# TABBx_Lure_1_0.net
KiCad netlist of a schematic drawn in EAGLE
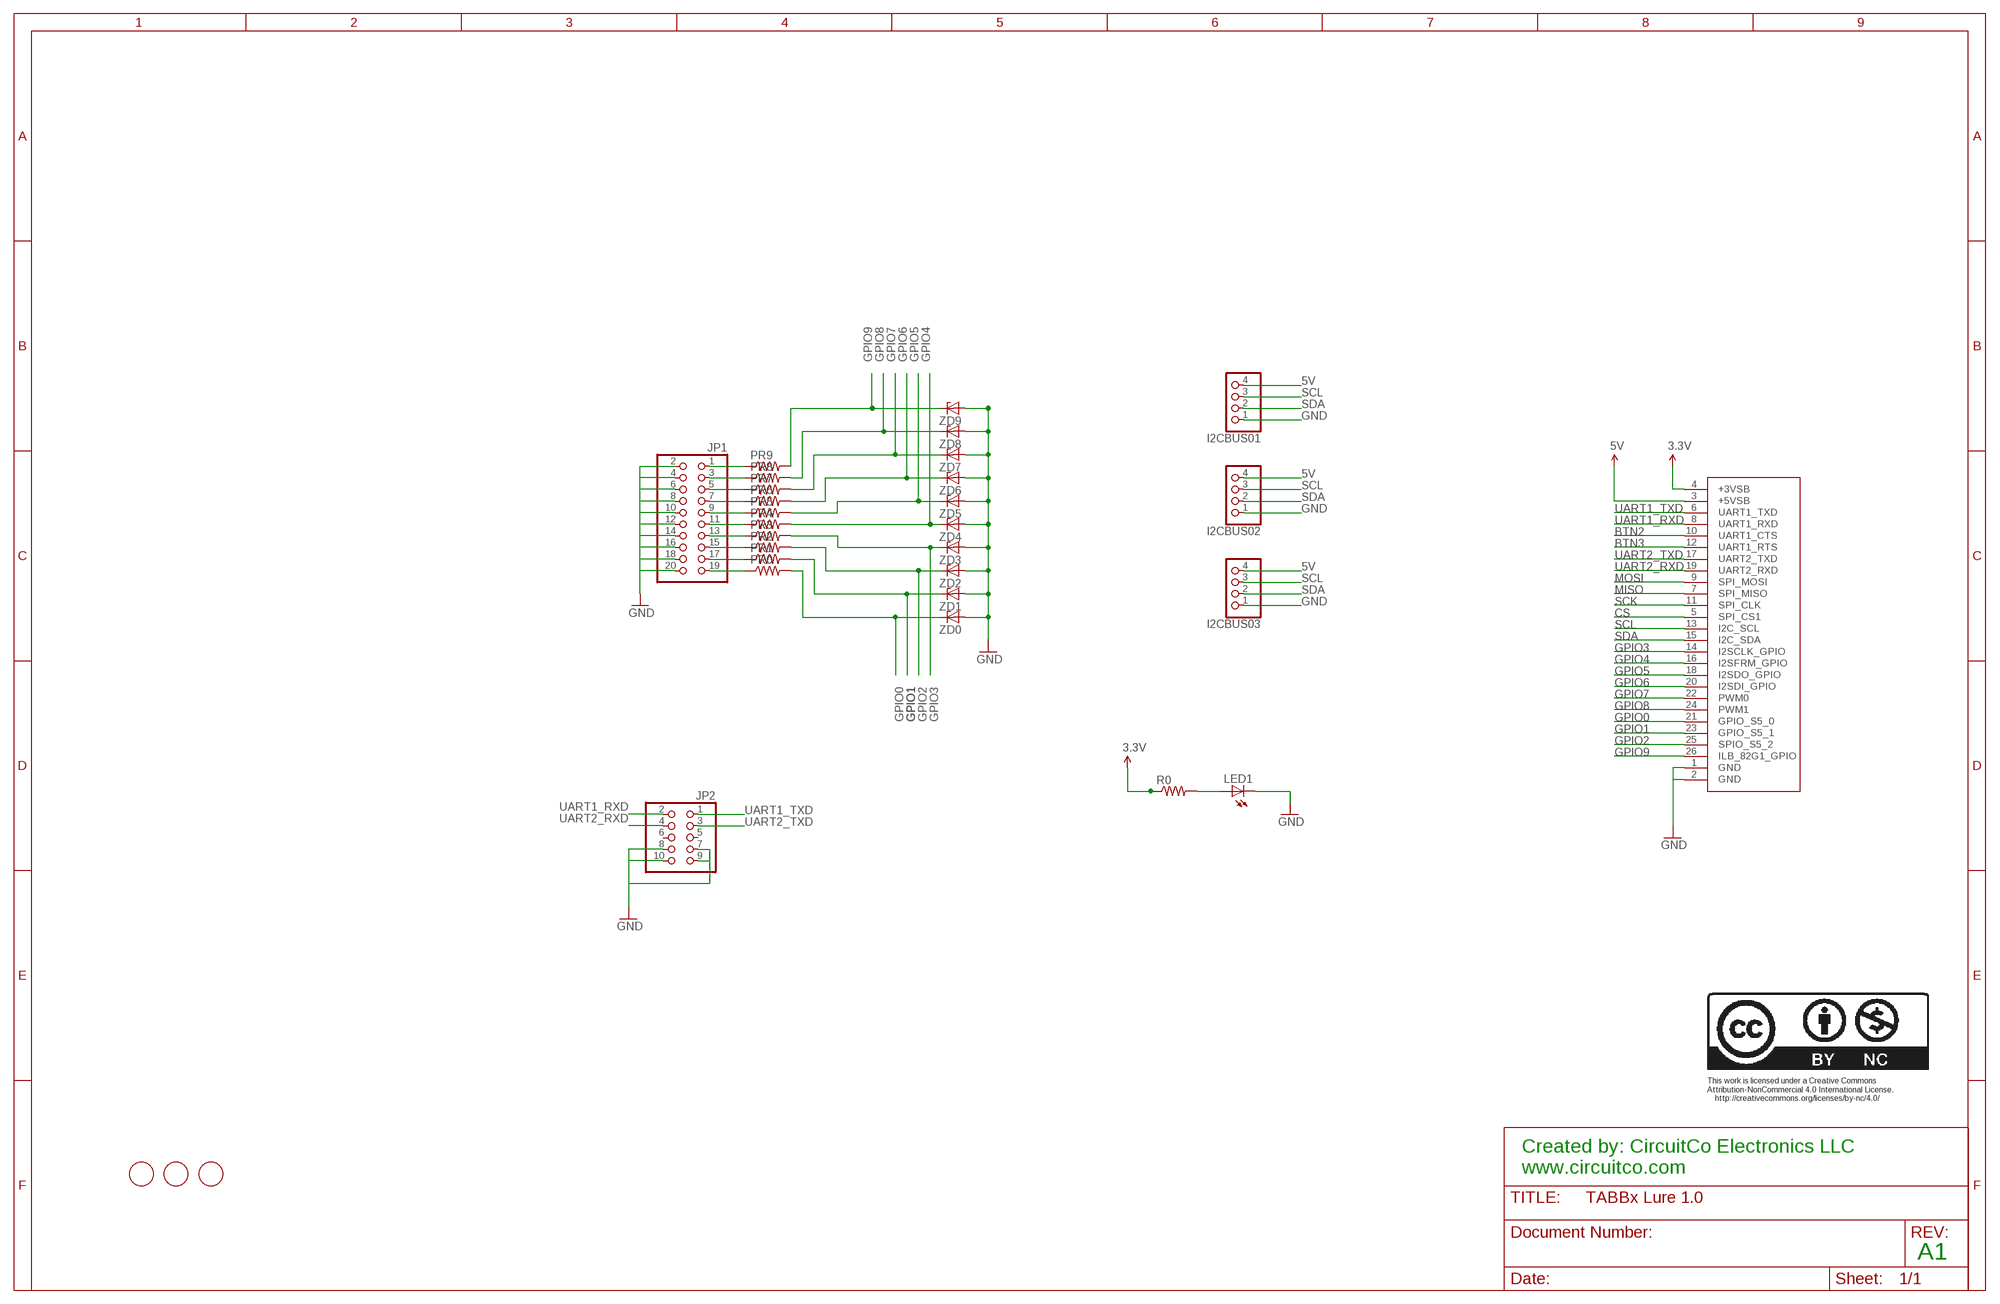
[diagram p0: schematic, sheet 1]

(export (version "E")
  (design (tool "Eeschema 10.0.6"))
  (components
    (comp (ref "I2CBUS01")
      (value "PINHD-1X4")
      (footprint "eagle-import:1X04")
      (libsource (lib "eagle-import") (part "PINHD-1X4"))
    )
    (comp (ref "I2CBUS02")
      (value "PINHD-1X4")
      (footprint "eagle-import:1X04")
      (libsource (lib "eagle-import") (part "PINHD-1X4"))
    )
    (comp (ref "I2CBUS03")
      (value "PINHD-1X4")
      (footprint "eagle-import:1X04")
      (libsource (lib "eagle-import") (part "PINHD-1X4"))
    )
    (comp (ref "JP1")
      (value "PINHD-2X10/90")
      (footprint "eagle-import:2X10_90")
      (libsource (lib "eagle-import") (part "PINHD-2X10/90"))
    )
    (comp (ref "JP2")
      (value "PINHD-2X5/90")
      (footprint "eagle-import:2X05_90")
      (libsource (lib "eagle-import") (part "PINHD-2X5/90"))
    )
    (comp (ref "JP4")
      (value "MINNOW2_LOW_SPEED")
      (footprint "eagle-import:MINNOWBOARD_2_LOW_SPEED")
      (libsource (lib "eagle-import") (part "MINNOW2_LOW_SPEED"))
    )
    (comp (ref "LED1")
      (value "LEDCHIPLED_1206")
      (footprint "eagle-import:CHIPLED_1206")
      (libsource (lib "eagle-import") (part "LEDCHIPLED_1206"))
    )
    (comp (ref "PR0")
      (value "R-US_M1206")
      (footprint "eagle-import:M1206")
      (libsource (lib "eagle-import") (part "R-US_M1206"))
    )
    (comp (ref "PR1")
      (value "R-US_M1206")
      (footprint "eagle-import:M1206")
      (libsource (lib "eagle-import") (part "R-US_M1206"))
    )
    (comp (ref "PR2")
      (value "R-US_M1206")
      (footprint "eagle-import:M1206")
      (libsource (lib "eagle-import") (part "R-US_M1206"))
    )
    (comp (ref "PR3")
      (value "R-US_M1206")
      (footprint "eagle-import:M1206")
      (libsource (lib "eagle-import") (part "R-US_M1206"))
    )
    (comp (ref "PR4")
      (value "R-US_M1206")
      (footprint "eagle-import:M1206")
      (libsource (lib "eagle-import") (part "R-US_M1206"))
    )
    (comp (ref "PR5")
      (value "R-US_M1206")
      (footprint "eagle-import:M1206")
      (libsource (lib "eagle-import") (part "R-US_M1206"))
    )
    (comp (ref "PR6")
      (value "R-US_M1206")
      (footprint "eagle-import:M1206")
      (libsource (lib "eagle-import") (part "R-US_M1206"))
    )
    (comp (ref "PR7")
      (value "R-US_M1206")
      (footprint "eagle-import:M1206")
      (libsource (lib "eagle-import") (part "R-US_M1206"))
    )
    (comp (ref "PR8")
      (value "R-US_M1206")
      (footprint "eagle-import:M1206")
      (libsource (lib "eagle-import") (part "R-US_M1206"))
    )
    (comp (ref "PR9")
      (value "R-US_M1206")
      (footprint "eagle-import:M1206")
      (libsource (lib "eagle-import") (part "R-US_M1206"))
    )
    (comp (ref "R0")
      (value "R-US_M1206")
      (footprint "eagle-import:M1206")
      (libsource (lib "eagle-import") (part "R-US_M1206"))
    )
    (comp (ref "U$3")
      (value "FIDUCIAL")
      (footprint "eagle-import:FIDUCIAL_1MM")
      (libsource (lib "eagle-import") (part "FIDUCIAL"))
    )
    (comp (ref "U$5")
      (value "FIDUCIAL")
      (footprint "eagle-import:FIDUCIAL_1MM")
      (libsource (lib "eagle-import") (part "FIDUCIAL"))
    )
    (comp (ref "U$6")
      (value "FIDUCIAL")
      (footprint "eagle-import:FIDUCIAL_1MM")
      (libsource (lib "eagle-import") (part "FIDUCIAL"))
    )
    (comp (ref "ZD0")
      (value "ZENER-DIODEDO35Z10")
      (footprint "eagle-import:DO35Z10")
      (libsource (lib "eagle-import") (part "ZENER-DIODEDO35Z10"))
    )
    (comp (ref "ZD1")
      (value "ZENER-DIODEDO35Z10")
      (footprint "eagle-import:DO35Z10")
      (libsource (lib "eagle-import") (part "ZENER-DIODEDO35Z10"))
    )
    (comp (ref "ZD2")
      (value "ZENER-DIODEDO35Z10")
      (footprint "eagle-import:DO35Z10")
      (libsource (lib "eagle-import") (part "ZENER-DIODEDO35Z10"))
    )
    (comp (ref "ZD3")
      (value "ZENER-DIODEDO35Z10")
      (footprint "eagle-import:DO35Z10")
      (libsource (lib "eagle-import") (part "ZENER-DIODEDO35Z10"))
    )
    (comp (ref "ZD4")
      (value "ZENER-DIODEDO35Z10")
      (footprint "eagle-import:DO35Z10")
      (libsource (lib "eagle-import") (part "ZENER-DIODEDO35Z10"))
    )
    (comp (ref "ZD5")
      (value "ZENER-DIODEDO35Z10")
      (footprint "eagle-import:DO35Z10")
      (libsource (lib "eagle-import") (part "ZENER-DIODEDO35Z10"))
    )
    (comp (ref "ZD6")
      (value "ZENER-DIODEDO35Z10")
      (footprint "eagle-import:DO35Z10")
      (libsource (lib "eagle-import") (part "ZENER-DIODEDO35Z10"))
    )
    (comp (ref "ZD7")
      (value "ZENER-DIODEDO35Z10")
      (footprint "eagle-import:DO35Z10")
      (libsource (lib "eagle-import") (part "ZENER-DIODEDO35Z10"))
    )
    (comp (ref "ZD8")
      (value "ZENER-DIODEDO35Z10")
      (footprint "eagle-import:DO35Z10")
      (libsource (lib "eagle-import") (part "ZENER-DIODEDO35Z10"))
    )
    (comp (ref "ZD9")
      (value "ZENER-DIODEDO35Z10")
      (footprint "eagle-import:DO35Z10")
      (libsource (lib "eagle-import") (part "ZENER-DIODEDO35Z10"))
    )
  )
  (nets
    (net (code "1") (name "/BTN2") (class "Default")
      (node (ref "JP4") (pin "10") (pinfunction "UART1_CTS_10") (pintype "bidirectional"))
    )
    (net (code "2") (name "/BTN3") (class "Default")
      (node (ref "JP4") (pin "12") (pinfunction "UART1_RTS_12") (pintype "bidirectional"))
    )
    (net (code "3") (name "/CS") (class "Default")
      (node (ref "JP4") (pin "5") (pinfunction "SPI_CS1_5") (pintype "bidirectional"))
    )
    (net (code "4") (name "/GPIO0") (class "Default")
      (node (ref "JP4") (pin "21") (pinfunction "GPIO_S5_0_21") (pintype "bidirectional"))
      (node (ref "PR0") (pin "2") (pinfunction "2_2") (pintype "passive"))
      (node (ref "ZD0") (pin "C") (pinfunction "C_C") (pintype "passive"))
    )
    (net (code "5") (name "/GPIO1") (class "Default")
      (node (ref "JP4") (pin "23") (pinfunction "GPIO_S5_1_23") (pintype "bidirectional"))
      (node (ref "PR1") (pin "2") (pinfunction "2_2") (pintype "passive"))
      (node (ref "ZD1") (pin "C") (pinfunction "C_C") (pintype "passive"))
    )
    (net (code "6") (name "/GPIO2") (class "Default")
      (node (ref "JP4") (pin "25") (pinfunction "SPIO_S5_2_25") (pintype "bidirectional"))
      (node (ref "PR2") (pin "2") (pinfunction "2_2") (pintype "passive"))
      (node (ref "ZD2") (pin "C") (pinfunction "C_C") (pintype "passive"))
    )
    (net (code "7") (name "/GPIO3") (class "Default")
      (node (ref "JP4") (pin "14") (pinfunction "I2SCLK_GPIO_14") (pintype "bidirectional"))
      (node (ref "PR3") (pin "2") (pinfunction "2_2") (pintype "passive"))
      (node (ref "ZD3") (pin "C") (pinfunction "C_C") (pintype "passive"))
    )
    (net (code "8") (name "/GPIO4") (class "Default")
      (node (ref "JP4") (pin "16") (pinfunction "I2SFRM_GPIO_16") (pintype "bidirectional"))
      (node (ref "PR4") (pin "2") (pinfunction "2_2") (pintype "passive"))
      (node (ref "ZD4") (pin "C") (pinfunction "C_C") (pintype "passive"))
    )
    (net (code "9") (name "/GPIO5") (class "Default")
      (node (ref "JP4") (pin "18") (pinfunction "I2SDO_GPIO_18") (pintype "bidirectional"))
      (node (ref "PR5") (pin "2") (pinfunction "2_2") (pintype "passive"))
      (node (ref "ZD5") (pin "C") (pinfunction "C_C") (pintype "passive"))
    )
    (net (code "10") (name "/GPIO6") (class "Default")
      (node (ref "JP4") (pin "20") (pinfunction "I2SDI_GPIO_20") (pintype "bidirectional"))
      (node (ref "PR6") (pin "2") (pinfunction "2_2") (pintype "passive"))
      (node (ref "ZD6") (pin "C") (pinfunction "C_C") (pintype "passive"))
    )
    (net (code "11") (name "/GPIO7") (class "Default")
      (node (ref "JP4") (pin "22") (pinfunction "PWM0_22") (pintype "bidirectional"))
      (node (ref "PR7") (pin "2") (pinfunction "2_2") (pintype "passive"))
      (node (ref "ZD7") (pin "C") (pinfunction "C_C") (pintype "passive"))
    )
    (net (code "12") (name "/GPIO8") (class "Default")
      (node (ref "JP4") (pin "24") (pinfunction "PWM1_24") (pintype "bidirectional"))
      (node (ref "PR8") (pin "2") (pinfunction "2_2") (pintype "passive"))
      (node (ref "ZD8") (pin "C") (pinfunction "C_C") (pintype "passive"))
    )
    (net (code "13") (name "/GPIO9") (class "Default")
      (node (ref "JP4") (pin "26") (pinfunction "ILB_82G1_GPIO_26") (pintype "bidirectional"))
      (node (ref "PR9") (pin "2") (pinfunction "2_2") (pintype "passive"))
      (node (ref "ZD9") (pin "C") (pinfunction "C_C") (pintype "passive"))
    )
    (net (code "14") (name "/MISO") (class "Default")
      (node (ref "JP4") (pin "7") (pinfunction "SPI_MISO_7") (pintype "bidirectional"))
    )
    (net (code "15") (name "/MOSI") (class "Default")
      (node (ref "JP4") (pin "9") (pinfunction "SPI_MOSI_9") (pintype "bidirectional"))
    )
    (net (code "16") (name "/SCK") (class "Default")
      (node (ref "JP4") (pin "11") (pinfunction "SPI_CLK_11") (pintype "bidirectional"))
    )
    (net (code "17") (name "/SCL") (class "Default")
      (node (ref "I2CBUS01") (pin "3") (pinfunction "3_3") (pintype "passive"))
      (node (ref "I2CBUS02") (pin "3") (pinfunction "3_3") (pintype "passive"))
      (node (ref "I2CBUS03") (pin "3") (pinfunction "3_3") (pintype "passive"))
      (node (ref "JP4") (pin "13") (pinfunction "I2C_SCL_13") (pintype "bidirectional"))
    )
    (net (code "18") (name "/SDA") (class "Default")
      (node (ref "I2CBUS01") (pin "2") (pinfunction "2_2") (pintype "passive"))
      (node (ref "I2CBUS02") (pin "2") (pinfunction "2_2") (pintype "passive"))
      (node (ref "I2CBUS03") (pin "2") (pinfunction "2_2") (pintype "passive"))
      (node (ref "JP4") (pin "15") (pinfunction "I2C_SDA_15") (pintype "bidirectional"))
    )
    (net (code "19") (name "/UART1_RXD") (class "Default")
      (node (ref "JP2") (pin "2") (pinfunction "2_2") (pintype "passive"))
      (node (ref "JP4") (pin "8") (pinfunction "UART1_RXD_8") (pintype "bidirectional"))
    )
    (net (code "20") (name "/UART1_TXD") (class "Default")
      (node (ref "JP2") (pin "1") (pinfunction "1_1") (pintype "passive"))
      (node (ref "JP4") (pin "6") (pinfunction "UART1_TXD_6") (pintype "bidirectional"))
    )
    (net (code "21") (name "/UART2_RXD") (class "Default")
      (node (ref "JP2") (pin "4") (pinfunction "4_4") (pintype "passive"))
      (node (ref "JP4") (pin "19") (pinfunction "UART2_RXD_19") (pintype "bidirectional"))
    )
    (net (code "22") (name "/UART2_TXD") (class "Default")
      (node (ref "JP2") (pin "3") (pinfunction "3_3") (pintype "passive"))
      (node (ref "JP4") (pin "17") (pinfunction "UART2_TXD_17") (pintype "bidirectional"))
    )
    (net (code "23") (name "3.3V") (class "Default")
      (node (ref "JP4") (pin "4") (pinfunction "+3VSB_4") (pintype "bidirectional"))
      (node (ref "R0") (pin "1") (pinfunction "1_1") (pintype "passive"))
    )
    (net (code "24") (name "5V") (class "Default")
      (node (ref "I2CBUS01") (pin "4") (pinfunction "4_4") (pintype "passive"))
      (node (ref "I2CBUS02") (pin "4") (pinfunction "4_4") (pintype "passive"))
      (node (ref "I2CBUS03") (pin "4") (pinfunction "4_4") (pintype "passive"))
      (node (ref "JP4") (pin "3") (pinfunction "+5VSB_3") (pintype "bidirectional"))
    )
    (net (code "25") (name "GND") (class "Default")
      (node (ref "I2CBUS01") (pin "1") (pinfunction "1_1") (pintype "passive"))
      (node (ref "I2CBUS02") (pin "1") (pinfunction "1_1") (pintype "passive"))
      (node (ref "I2CBUS03") (pin "1") (pinfunction "1_1") (pintype "passive"))
      (node (ref "JP1") (pin "10") (pinfunction "10_10") (pintype "passive"))
      (node (ref "JP1") (pin "12") (pinfunction "12_12") (pintype "passive"))
      (node (ref "JP1") (pin "14") (pinfunction "14_14") (pintype "passive"))
      (node (ref "JP1") (pin "16") (pinfunction "16_16") (pintype "passive"))
      (node (ref "JP1") (pin "18") (pinfunction "18_18") (pintype "passive"))
      (node (ref "JP1") (pin "2") (pinfunction "2_2") (pintype "passive"))
      (node (ref "JP1") (pin "20") (pinfunction "20_20") (pintype "passive"))
      (node (ref "JP1") (pin "4") (pinfunction "4_4") (pintype "passive"))
      (node (ref "JP1") (pin "6") (pinfunction "6_6") (pintype "passive"))
      (node (ref "JP1") (pin "8") (pinfunction "8_8") (pintype "passive"))
      (node (ref "JP2") (pin "10") (pinfunction "10_10") (pintype "passive"))
      (node (ref "JP2") (pin "7") (pinfunction "7_7") (pintype "passive"))
      (node (ref "JP2") (pin "8") (pinfunction "8_8") (pintype "passive"))
      (node (ref "JP2") (pin "9") (pinfunction "9_9") (pintype "passive"))
      (node (ref "JP4") (pin "1") (pinfunction "GND_1") (pintype "bidirectional"))
      (node (ref "JP4") (pin "2") (pinfunction "GND_2") (pintype "bidirectional"))
      (node (ref "LED1") (pin "C") (pinfunction "C_C") (pintype "passive"))
      (node (ref "ZD0") (pin "A") (pinfunction "A_A") (pintype "passive"))
      (node (ref "ZD1") (pin "A") (pinfunction "A_A") (pintype "passive"))
      (node (ref "ZD2") (pin "A") (pinfunction "A_A") (pintype "passive"))
      (node (ref "ZD3") (pin "A") (pinfunction "A_A") (pintype "passive"))
      (node (ref "ZD4") (pin "A") (pinfunction "A_A") (pintype "passive"))
      (node (ref "ZD5") (pin "A") (pinfunction "A_A") (pintype "passive"))
      (node (ref "ZD6") (pin "A") (pinfunction "A_A") (pintype "passive"))
      (node (ref "ZD7") (pin "A") (pinfunction "A_A") (pintype "passive"))
      (node (ref "ZD8") (pin "A") (pinfunction "A_A") (pintype "passive"))
      (node (ref "ZD9") (pin "A") (pinfunction "A_A") (pintype "passive"))
    )
    (net (code "26") (name "Net-(JP1-Pad1)") (class "Default")
      (node (ref "JP1") (pin "1") (pinfunction "1_1") (pintype "passive"))
      (node (ref "PR9") (pin "1") (pinfunction "1_1") (pintype "passive"))
    )
    (net (code "27") (name "Net-(JP1-Pad3)") (class "Default")
      (node (ref "JP1") (pin "3") (pinfunction "3_3") (pintype "passive"))
      (node (ref "PR8") (pin "1") (pinfunction "1_1") (pintype "passive"))
    )
    (net (code "28") (name "Net-(JP1-Pad5)") (class "Default")
      (node (ref "JP1") (pin "5") (pinfunction "5_5") (pintype "passive"))
      (node (ref "PR7") (pin "1") (pinfunction "1_1") (pintype "passive"))
    )
    (net (code "29") (name "Net-(JP1-Pad7)") (class "Default")
      (node (ref "JP1") (pin "7") (pinfunction "7_7") (pintype "passive"))
      (node (ref "PR6") (pin "1") (pinfunction "1_1") (pintype "passive"))
    )
    (net (code "30") (name "Net-(JP1-Pad9)") (class "Default")
      (node (ref "JP1") (pin "9") (pinfunction "9_9") (pintype "passive"))
      (node (ref "PR5") (pin "1") (pinfunction "1_1") (pintype "passive"))
    )
    (net (code "31") (name "Net-(JP1-Pad11)") (class "Default")
      (node (ref "JP1") (pin "11") (pinfunction "11_11") (pintype "passive"))
      (node (ref "PR4") (pin "1") (pinfunction "1_1") (pintype "passive"))
    )
    (net (code "32") (name "Net-(JP1-Pad13)") (class "Default")
      (node (ref "JP1") (pin "13") (pinfunction "13_13") (pintype "passive"))
      (node (ref "PR3") (pin "1") (pinfunction "1_1") (pintype "passive"))
    )
    (net (code "33") (name "Net-(JP1-Pad15)") (class "Default")
      (node (ref "JP1") (pin "15") (pinfunction "15_15") (pintype "passive"))
      (node (ref "PR2") (pin "1") (pinfunction "1_1") (pintype "passive"))
    )
    (net (code "34") (name "Net-(JP1-Pad17)") (class "Default")
      (node (ref "JP1") (pin "17") (pinfunction "17_17") (pintype "passive"))
      (node (ref "PR1") (pin "1") (pinfunction "1_1") (pintype "passive"))
    )
    (net (code "35") (name "Net-(JP1-Pad19)") (class "Default")
      (node (ref "JP1") (pin "19") (pinfunction "19_19") (pintype "passive"))
      (node (ref "PR0") (pin "1") (pinfunction "1_1") (pintype "passive"))
    )
    (net (code "36") (name "Net-(LED1-PadA)") (class "Default")
      (node (ref "LED1") (pin "A") (pinfunction "A_A") (pintype "passive"))
      (node (ref "R0") (pin "2") (pinfunction "2_2") (pintype "passive"))
    )
    (net (code "37") (name "unconnected-(JP2-Pad5)") (class "Default")
      (node (ref "JP2") (pin "5") (pinfunction "5_5") (pintype "passive"))
    )
    (net (code "38") (name "unconnected-(JP2-Pad6)") (class "Default")
      (node (ref "JP2") (pin "6") (pinfunction "6_6") (pintype "passive"))
    )
  )
)
